# 09-AD9513-2.net
KiCad netlist of a schematic drawn in Altium Designer
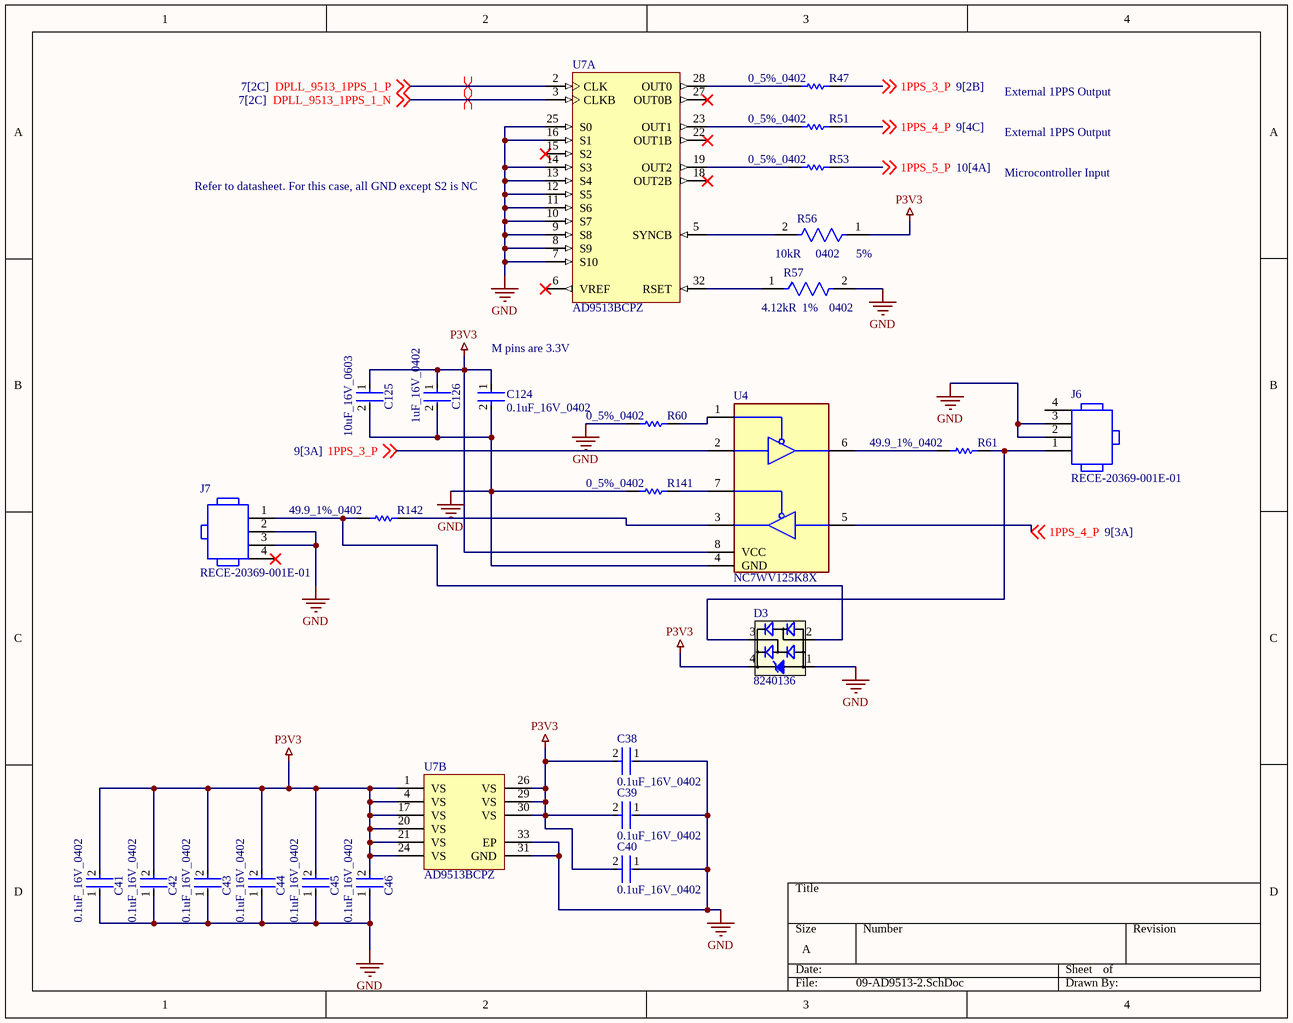
[diagram p0: 09-AD9513-2.SchDoc]

(export (version "E")
  (design (tool "Eeschema 10.0.6"))
  (components
    (comp (ref "C38")
      (value "0.1uF_16V_0402")
      (footprint "FP-GRM15-MFG")
      (description "CAP CER 0.1UF 16V X7R 0402")
      (fields (field (name "MANUFACTURER PART NUMBER") "GRM155R71C104KA88D") (field (name "TOLERANCE") "10%"))
      (libsource (lib "Altium Content Vault") (part "236180d848d6139a670b325ea6854c9"))
    )
    (comp (ref "C39")
      (value "0.1uF_16V_0402")
      (footprint "FP-GRM15-MFG")
      (description "CAP CER 0.1UF 16V X7R 0402")
      (fields (field (name "MANUFACTURER PART NUMBER") "GRM155R71C104KA88D") (field (name "TOLERANCE") "10%"))
      (libsource (lib "Altium Content Vault") (part "236180d848d6139a670b325ea6854c9"))
    )
    (comp (ref "C40")
      (value "0.1uF_16V_0402")
      (footprint "FP-GRM15-MFG")
      (description "CAP CER 0.1UF 16V X7R 0402")
      (fields (field (name "MANUFACTURER PART NUMBER") "GRM155R71C104KA88D") (field (name "TOLERANCE") "10%"))
      (libsource (lib "Altium Content Vault") (part "236180d848d6139a670b325ea6854c9"))
    )
    (comp (ref "C41")
      (value "0.1uF_16V_0402")
      (footprint "FP-GRM15-MFG")
      (description "CAP CER 0.1UF 16V X7R 0402")
      (fields (field (name "MANUFACTURER PART NUMBER") "GRM155R71C104KA88D") (field (name "TOLERANCE") "10%"))
      (libsource (lib "Altium Content Vault") (part "236180d848d6139a670b325ea6854c9"))
    )
    (comp (ref "C42")
      (value "0.1uF_16V_0402")
      (footprint "FP-GRM15-MFG")
      (description "CAP CER 0.1UF 16V X7R 0402")
      (fields (field (name "MANUFACTURER PART NUMBER") "GRM155R71C104KA88D") (field (name "TOLERANCE") "10%"))
      (libsource (lib "Altium Content Vault") (part "236180d848d6139a670b325ea6854c9"))
    )
    (comp (ref "C43")
      (value "0.1uF_16V_0402")
      (footprint "FP-GRM15-MFG")
      (description "CAP CER 0.1UF 16V X7R 0402")
      (fields (field (name "MANUFACTURER PART NUMBER") "GRM155R71C104KA88D") (field (name "TOLERANCE") "10%"))
      (libsource (lib "Altium Content Vault") (part "236180d848d6139a670b325ea6854c9"))
    )
    (comp (ref "C44")
      (value "0.1uF_16V_0402")
      (footprint "FP-GRM15-MFG")
      (description "CAP CER 0.1UF 16V X7R 0402")
      (fields (field (name "MANUFACTURER PART NUMBER") "GRM155R71C104KA88D") (field (name "TOLERANCE") "10%"))
      (libsource (lib "Altium Content Vault") (part "236180d848d6139a670b325ea6854c9"))
    )
    (comp (ref "C45")
      (value "0.1uF_16V_0402")
      (footprint "FP-GRM15-MFG")
      (description "CAP CER 0.1UF 16V X7R 0402")
      (fields (field (name "MANUFACTURER PART NUMBER") "GRM155R71C104KA88D") (field (name "TOLERANCE") "10%"))
      (libsource (lib "Altium Content Vault") (part "236180d848d6139a670b325ea6854c9"))
    )
    (comp (ref "C46")
      (value "0.1uF_16V_0402")
      (footprint "FP-GRM15-MFG")
      (description "CAP CER 0.1UF 16V X7R 0402")
      (fields (field (name "MANUFACTURER PART NUMBER") "GRM155R71C104KA88D") (field (name "TOLERANCE") "10%"))
      (libsource (lib "Altium Content Vault") (part "236180d848d6139a670b325ea6854c9"))
    )
    (comp (ref "C124")
      (value "GRM155R71C104KA88D")
      (footprint "FP-GRM15-MFG")
      (description "CAP CER 0.1UF 16V X7R 0402")
      (fields
        (field (name "TOLERANCE") "10%")
        (field (name "OCTOPART") "https://octopart.com/grm155r71c104ka88d-murata-196880")
        (field (name "DIGIKEY DESCRIPTION") "0.1uF_16V_0402")
      )
      (libsource (lib "Altium Content Vault") (part "236180d848d6139a670b325ea6854c9"))
    )
    (comp (ref "C125")
      (value "10uF_16V_0603")
      (footprint "FP-C1608-MFG")
      (description "CAP CER 10UF 16V X5R 0603")
      (fields
        (field (name "OCTOPART") "https://octopart.com/c1608x5r1c106m080ab-tdk-26013480")
        (field (name "MANUFACTURER") "TDK Corporation")
      )
      (libsource (lib "Altium Content Vault") (part "11868f565c42a9108669ba33697ecf6"))
    )
    (comp (ref "C126")
      (value "1uF_16V_0402")
      (footprint "FP-0402-L_1_0_0_05-W_0_5-IPC_C")
      (description "None")
      (fields (field (name "TOLERANCE") "20%") (field (name "VOLTAGE") "16V"))
      (libsource (lib "Altium Content Vault") (part "b4654b650e69147ec39a6b967a45e02"))
    )
    (comp (ref "D3")
      (value "8240136")
      (footprint "SOT143-4L")
      (description "TVS Diode WE-TVS-HS, VRWM=3.3V")
      (fields (field (name "MANUFACTURER") "Wuerth Elektronik"))
      (libsource (lib "Altium Content Vault") (part "WE-TVS-HS-4"))
    )
    (comp (ref "J6")
      (value "RECE-20369-001E-01")
      (footprint "TG-RECE-20369-001E-4_V")
      (description "RF Connector, Onboard Receptacle, IPEX MHFIII")
      (fields (field (name "MANUFACTURER") "Taoglas"))
      (libsource (lib "Altium Content Vault") (part "TG-RECE-20369-001E-01-4"))
    )
    (comp (ref "J7")
      (value "RECE-20369-001E-01")
      (footprint "TG-RECE-20369-001E-4_V")
      (description "RF Connector, Onboard Receptacle, IPEX MHFIII")
      (fields (field (name "MANUFACTURER") "Taoglas"))
      (libsource (lib "Altium Content Vault") (part "TG-RECE-20369-001E-01-4"))
    )
    (comp (ref "R47")
      (value "0_5%_0402")
      (footprint "RESC1005X40X25LL10T10")
      (fields (field (name "MANUFACTURER") "KOA Speer") (field (name "PART NUMBER") "RK73Z1ETTP"))
      (libsource (lib "Altium Content Vault") (part "RES"))
    )
    (comp (ref "R51")
      (value "0_5%_0402")
      (footprint "RESC1005X40X25LL10T10")
      (fields (field (name "MANUFACTURER") "KOA Speer") (field (name "PART NUMBER") "RK73Z1ETTP"))
      (libsource (lib "Altium Content Vault") (part "RES"))
    )
    (comp (ref "R53")
      (value "0_5%_0402")
      (footprint "RESC1005X40X25LL10T10")
      (fields (field (name "MANUFACTURER") "KOA Speer") (field (name "PART NUMBER") "RK73Z1ETTP"))
      (libsource (lib "Altium Content Vault") (part "RES"))
    )
    (comp (ref "R56")
      (value "CRCW040210K0JNED")
      (footprint "FP-CRCW0402-e3-IPC_B")
      (description "RES Thick Film, 10kΩ, 5%, 0.063W, 200ppm/°C, 0402")
      (fields
        (field (name "CASE/PACKAGE") "0402")
        (field (name "RESISTANCE") "10kR")
        (field (name "TOLERANCE") "5%")
      )
      (libsource (lib "Altium Content Vault") (part "1029c3af85768c4190bb7ad29bc67b5"))
    )
    (comp (ref "R57")
      (value "CRCW04024K12FKED")
      (footprint "FP-CRCW0402-e3-IPC_A")
      (description "RES Thick Film, 4.12kΩ, 1%, 0.063W, 100ppm/°C, 0402")
      (fields
        (field (name "RESISTANCE") "4.12kR")
        (field (name "CASE/PACKAGE") "0402")
        (field (name "TOLERANCE") "1%")
      )
      (libsource (lib "Altium Content Vault") (part "1029c3af85768c4190bb7ad29bc67b5"))
    )
    (comp (ref "R60")
      (value "0_5%_0402")
      (footprint "RESC1005X40X25LL10T10")
      (fields (field (name "MANUFACTURER") "KOA Speer") (field (name "PART NUMBER") "RK73Z1ETTP"))
      (libsource (lib "Altium Content Vault") (part "RES"))
    )
    (comp (ref "R61")
      (value "49.9_1%_0402")
      (footprint "RESC1005X40X25NL05T05")
      (fields (field (name "MANUFACTURER") "Panasonic") (field (name "PART NUMBER") "ERJ-2RKF49R9X"))
      (libsource (lib "Altium Content Vault") (part "RES"))
    )
    (comp (ref "R141")
      (value "0_5%_0402")
      (footprint "RESC1005X40X25LL10T10")
      (fields (field (name "MANUFACTURER") "KOA Speer") (field (name "PART NUMBER") "RK73Z1ETTP"))
      (libsource (lib "Altium Content Vault") (part "RES"))
    )
    (comp (ref "R142")
      (value "49.9_1%_0402")
      (footprint "RESC1005X40X25NL05T05")
      (fields (field (name "MANUFACTURER") "Panasonic") (field (name "PART NUMBER") "ERJ-2RKF49R9X"))
      (libsource (lib "Altium Content Vault") (part "RES"))
    )
    (comp (ref "U4")
      (value "NC7WV125K8X")
      (footprint "NC7WV125")
      (description "Integrated Circuit")
      (fields (field (name "MOUSER PART NUMBER") "512-NC7WV125K8X"))
      (libsource (lib "SamacSys") (part "NC7WV125K8X"))
    )
    (comp (ref "U7")
      (value "AD9513BCPZ")
      (footprint "ADI-CP-32-2_N")
      (fields (field (name "MANUFACTURER") "Analog Devices"))
      (libsource (lib "Altium Content Vault") (part "ADI-AD9513-CP-32-2"))
    )
  )
  (nets
    (net (code "1") (name "1PPS_3_P") (class "Default")
      (node (ref "R47") (pin "2") (pinfunction "2_2") (pintype "passive"))
      (node (ref "U4") (pin "2") (pintype "passive"))
    )
    (net (code "2") (name "1PPS_4_P") (class "Default")
      (node (ref "R51") (pin "2") (pinfunction "2_2") (pintype "passive"))
      (node (ref "U4") (pin "5") (pintype "passive"))
    )
    (net (code "3") (name "1PPS_5_P") (class "Default")
      (node (ref "R53") (pin "2") (pinfunction "2_2") (pintype "passive"))
    )
    (net (code "4") (name "DPLL_9513_1PPS_1_N") (class "Default")
      (node (ref "U7") (pin "3") (pinfunction "CLKB_3") (pintype "input"))
    )
    (net (code "5") (name "DPLL_9513_1PPS_1_P") (class "Default")
      (node (ref "U7") (pin "2") (pinfunction "CLK_2") (pintype "input"))
    )
    (net (code "6") (name "GND") (class "Default")
      (node (ref "C124") (pin "2") (pinfunction "2_2") (pintype "passive"))
      (node (ref "C125") (pin "2") (pinfunction "2_2") (pintype "passive"))
      (node (ref "C126") (pin "2") (pinfunction "2_2") (pintype "passive"))
      (node (ref "C38") (pin "1") (pinfunction "1_1") (pintype "passive"))
      (node (ref "C39") (pin "1") (pinfunction "1_1") (pintype "passive"))
      (node (ref "C40") (pin "1") (pinfunction "1_1") (pintype "passive"))
      (node (ref "C41") (pin "1") (pinfunction "1_1") (pintype "passive"))
      (node (ref "C42") (pin "1") (pinfunction "1_1") (pintype "passive"))
      (node (ref "C43") (pin "1") (pinfunction "1_1") (pintype "passive"))
      (node (ref "C44") (pin "1") (pinfunction "1_1") (pintype "passive"))
      (node (ref "C45") (pin "1") (pinfunction "1_1") (pintype "passive"))
      (node (ref "C46") (pin "1") (pinfunction "1_1") (pintype "passive"))
      (node (ref "D3") (pin "1") (pinfunction "GND_1") (pintype "passive"))
      (node (ref "J6") (pin "2") (pinfunction "2_2") (pintype "passive"))
      (node (ref "J6") (pin "3") (pinfunction "3_3") (pintype "passive"))
      (node (ref "J7") (pin "2") (pinfunction "2_2") (pintype "passive"))
      (node (ref "J7") (pin "3") (pinfunction "3_3") (pintype "passive"))
      (node (ref "R141") (pin "1") (pinfunction "1_1") (pintype "passive"))
      (node (ref "R57") (pin "2") (pinfunction "2_2") (pintype "passive"))
      (node (ref "R60") (pin "1") (pinfunction "1_1") (pintype "passive"))
      (node (ref "U4") (pin "4") (pinfunction "GND_4") (pintype "passive"))
      (node (ref "U7") (pin "10") (pinfunction "S7_10") (pintype "input"))
      (node (ref "U7") (pin "11") (pinfunction "S6_11") (pintype "input"))
      (node (ref "U7") (pin "12") (pinfunction "S5_12") (pintype "input"))
      (node (ref "U7") (pin "13") (pinfunction "S4_13") (pintype "input"))
      (node (ref "U7") (pin "14") (pinfunction "S3_14") (pintype "input"))
      (node (ref "U7") (pin "16") (pinfunction "S1_16") (pintype "input"))
      (node (ref "U7") (pin "25") (pinfunction "S0_25") (pintype "input"))
      (node (ref "U7") (pin "31") (pinfunction "GND_31") (pintype "power_in"))
      (node (ref "U7") (pin "33") (pinfunction "EP_33") (pintype "power_in"))
      (node (ref "U7") (pin "7") (pinfunction "S10_7") (pintype "input"))
      (node (ref "U7") (pin "8") (pinfunction "S9_8") (pintype "input"))
      (node (ref "U7") (pin "9") (pinfunction "S8_9") (pintype "input"))
    )
    (net (code "7") (name "Net-(D3-I{slash}O1)") (class "Default")
      (node (ref "D3") (pin "2") (pinfunction "I/O1_2") (pintype "passive"))
      (node (ref "J7") (pin "1") (pinfunction "1_1") (pintype "passive"))
      (node (ref "R142") (pin "2") (pinfunction "2_2") (pintype "passive"))
    )
    (net (code "8") (name "Net-(D3-I{slash}O2)") (class "Default")
      (node (ref "D3") (pin "3") (pinfunction "I/O2_3") (pintype "passive"))
      (node (ref "J6") (pin "1") (pinfunction "1_1") (pintype "passive"))
      (node (ref "R61") (pin "1") (pinfunction "1_1") (pintype "passive"))
    )
    (net (code "9") (name "Net-(R60-Pad2)") (class "Default")
      (node (ref "R60") (pin "2") (pinfunction "2_2") (pintype "passive"))
      (node (ref "U4") (pin "1") (pintype "passive"))
    )
    (net (code "10") (name "Net-(R61-Pad2)") (class "Default")
      (node (ref "R61") (pin "2") (pinfunction "2_2") (pintype "passive"))
      (node (ref "U4") (pin "6") (pintype "passive"))
    )
    (net (code "11") (name "Net-(R141-Pad2)") (class "Default")
      (node (ref "R141") (pin "2") (pinfunction "2_2") (pintype "passive"))
      (node (ref "U4") (pin "7") (pintype "passive"))
    )
    (net (code "12") (name "Net-(R142-Pad1)") (class "Default")
      (node (ref "R142") (pin "1") (pinfunction "1_1") (pintype "passive"))
      (node (ref "U4") (pin "3") (pintype "passive"))
    )
    (net (code "13") (name "Net-(U7A-OUT0)") (class "Default")
      (node (ref "R47") (pin "1") (pinfunction "1_1") (pintype "passive"))
      (node (ref "U7") (pin "28") (pinfunction "OUT0_28") (pintype "output"))
    )
    (net (code "14") (name "Net-(U7A-OUT1)") (class "Default")
      (node (ref "R51") (pin "1") (pinfunction "1_1") (pintype "passive"))
      (node (ref "U7") (pin "23") (pinfunction "OUT1_23") (pintype "output"))
    )
    (net (code "15") (name "Net-(U7A-OUT2)") (class "Default")
      (node (ref "R53") (pin "1") (pinfunction "1_1") (pintype "passive"))
      (node (ref "U7") (pin "19") (pinfunction "OUT2_19") (pintype "output"))
    )
    (net (code "16") (name "Net-(U7A-RSET)") (class "Default")
      (node (ref "R57") (pin "1") (pinfunction "1_1") (pintype "passive"))
      (node (ref "U7") (pin "32") (pinfunction "RSET_32") (pintype "input"))
    )
    (net (code "17") (name "Net-(U7A-SYNCB)") (class "Default")
      (node (ref "R56") (pin "2") (pinfunction "2_2") (pintype "passive"))
      (node (ref "U7") (pin "5") (pinfunction "SYNCB_5") (pintype "input"))
    )
    (net (code "18") (name "P3V3") (class "Default")
      (node (ref "C124") (pin "1") (pinfunction "1_1") (pintype "passive"))
      (node (ref "C125") (pin "1") (pinfunction "1_1") (pintype "passive"))
      (node (ref "C126") (pin "1") (pinfunction "1_1") (pintype "passive"))
      (node (ref "C38") (pin "2") (pinfunction "2_2") (pintype "passive"))
      (node (ref "C39") (pin "2") (pinfunction "2_2") (pintype "passive"))
      (node (ref "C40") (pin "2") (pinfunction "2_2") (pintype "passive"))
      (node (ref "C41") (pin "2") (pinfunction "2_2") (pintype "passive"))
      (node (ref "C42") (pin "2") (pinfunction "2_2") (pintype "passive"))
      (node (ref "C43") (pin "2") (pinfunction "2_2") (pintype "passive"))
      (node (ref "C44") (pin "2") (pinfunction "2_2") (pintype "passive"))
      (node (ref "C45") (pin "2") (pinfunction "2_2") (pintype "passive"))
      (node (ref "C46") (pin "2") (pinfunction "2_2") (pintype "passive"))
      (node (ref "D3") (pin "4") (pinfunction "VDD_4") (pintype "passive"))
      (node (ref "R56") (pin "1") (pinfunction "1_1") (pintype "passive"))
      (node (ref "U4") (pin "8") (pinfunction "VCC_8") (pintype "passive"))
      (node (ref "U7") (pin "1") (pinfunction "VS_1") (pintype "power_in"))
      (node (ref "U7") (pin "17") (pinfunction "VS_17") (pintype "power_in"))
      (node (ref "U7") (pin "20") (pinfunction "VS_20") (pintype "power_in"))
      (node (ref "U7") (pin "21") (pinfunction "VS_21") (pintype "power_in"))
      (node (ref "U7") (pin "24") (pinfunction "VS_24") (pintype "power_in"))
      (node (ref "U7") (pin "26") (pinfunction "VS_26") (pintype "power_in"))
      (node (ref "U7") (pin "29") (pinfunction "VS_29") (pintype "power_in"))
      (node (ref "U7") (pin "30") (pinfunction "VS_30") (pintype "power_in"))
      (node (ref "U7") (pin "4") (pinfunction "VS_4") (pintype "power_in"))
    )
    (net (code "19") (name "unconnected-(J6-Pad4)") (class "Default")
      (node (ref "J6") (pin "4") (pinfunction "4_4") (pintype "passive"))
    )
    (net (code "20") (name "unconnected-(J7-Pad4)") (class "Default")
      (node (ref "J7") (pin "4") (pinfunction "4_4") (pintype "passive+no_connect"))
    )
    (net (code "21") (name "unconnected-(U7A-OUT0B-Pad27)") (class "Default")
      (node (ref "U7") (pin "27") (pinfunction "OUT0B_27") (pintype "output+no_connect"))
    )
    (net (code "22") (name "unconnected-(U7A-OUT1B-Pad22)") (class "Default")
      (node (ref "U7") (pin "22") (pinfunction "OUT1B_22") (pintype "output+no_connect"))
    )
    (net (code "23") (name "unconnected-(U7A-OUT2B-Pad18)") (class "Default")
      (node (ref "U7") (pin "18") (pinfunction "OUT2B_18") (pintype "output+no_connect"))
    )
    (net (code "24") (name "unconnected-(U7A-S2-Pad15)") (class "Default")
      (node (ref "U7") (pin "15") (pinfunction "S2_15") (pintype "input+no_connect"))
    )
    (net (code "25") (name "unconnected-(U7A-VREF-Pad6)") (class "Default")
      (node (ref "U7") (pin "6") (pinfunction "VREF_6") (pintype "output+no_connect"))
    )
  )
)
